# poe_breakout.net
KiCad netlist of a schematic drawn in EAGLE
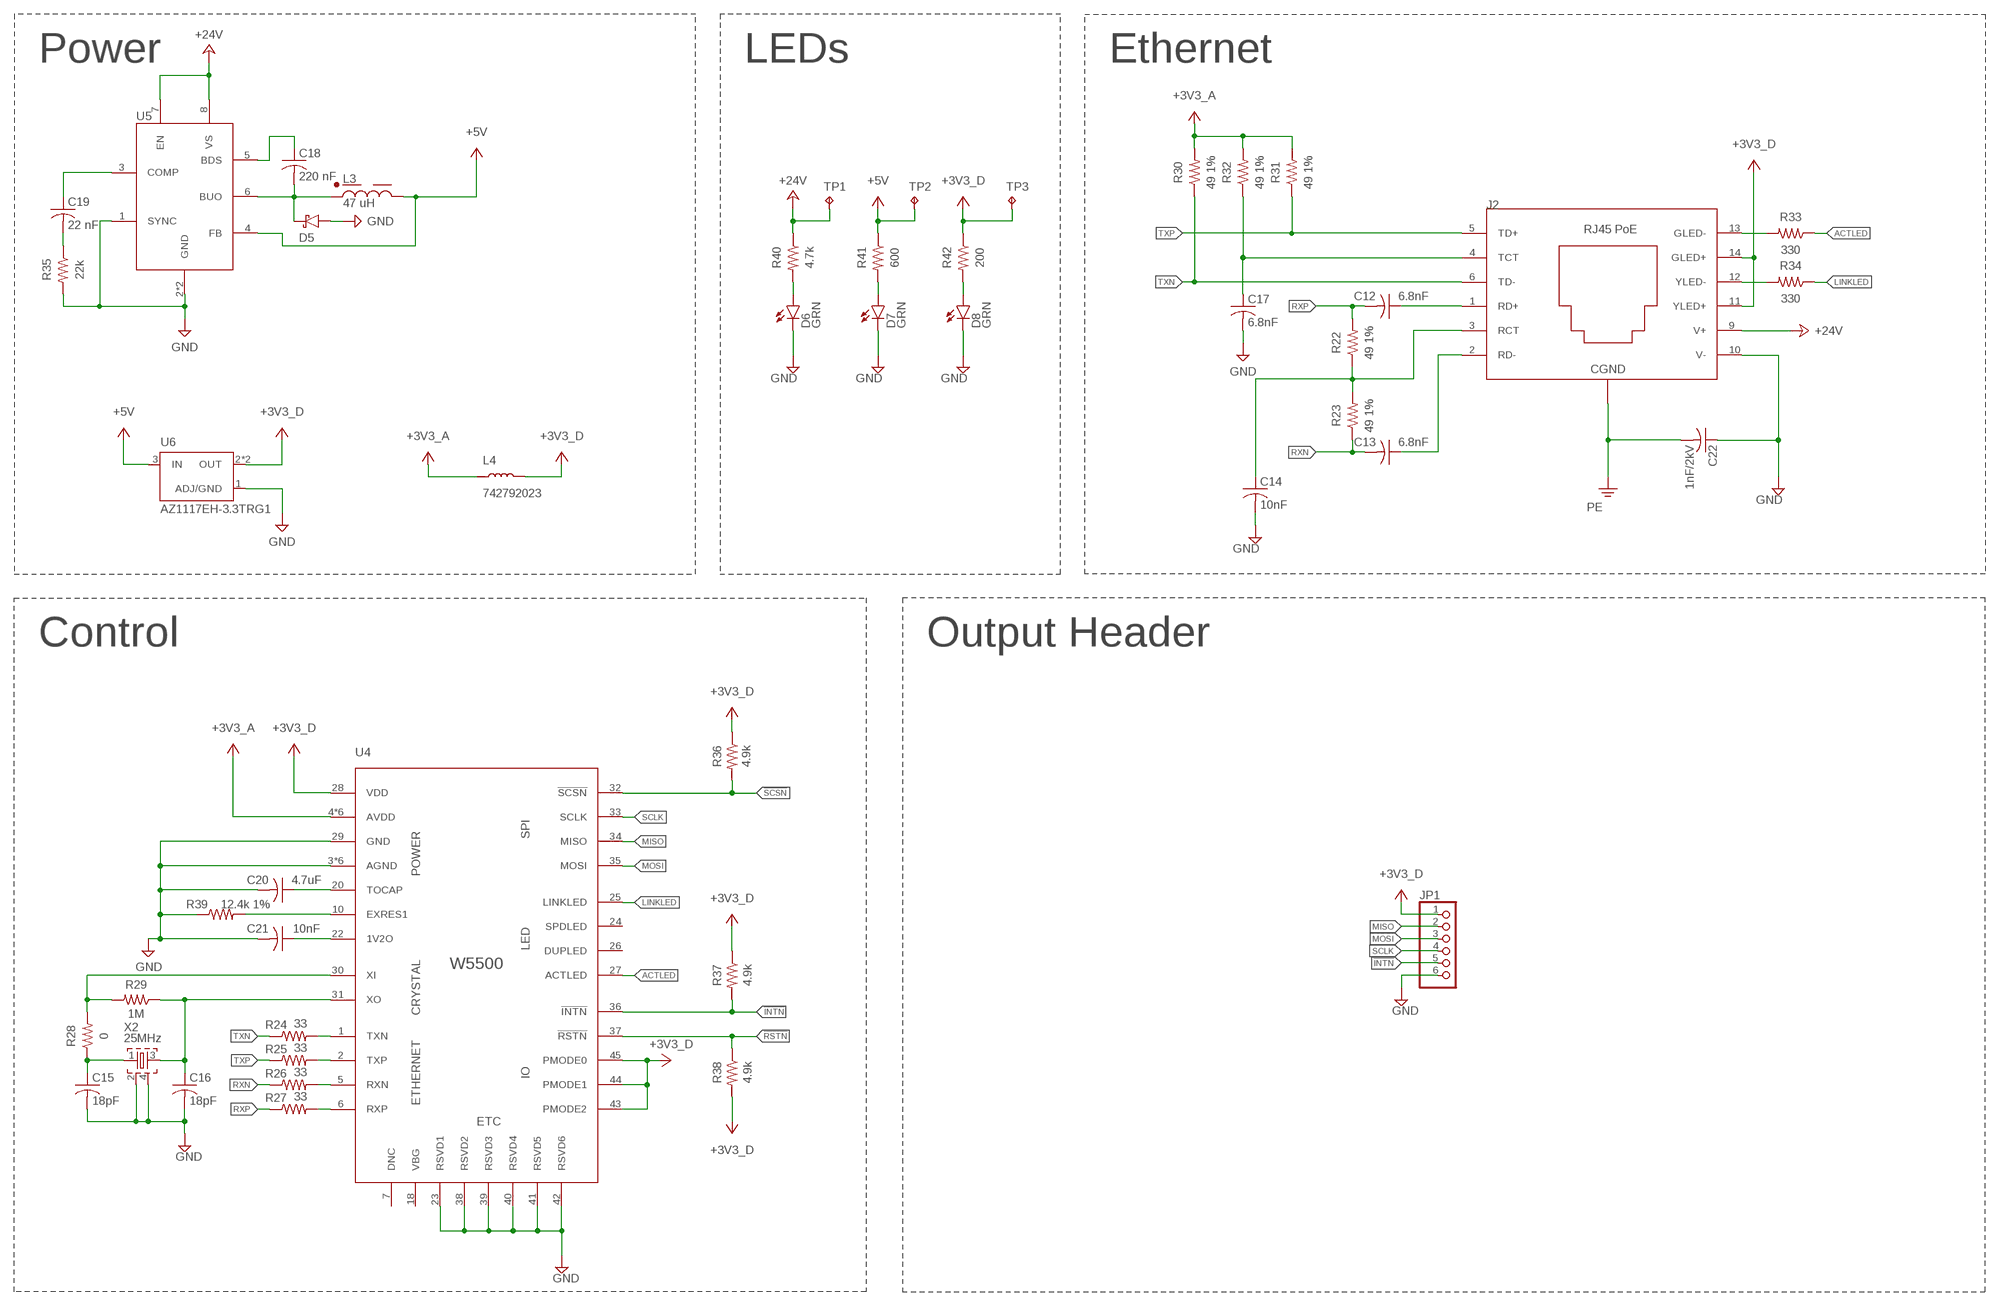
[diagram p0: schematic, sheet 1]

(export (version "E")
  (design (tool "Eeschema 10.0.6"))
  (components
    (comp (ref "C12")
      (value "6.8nF")
      (footprint "eagle-import:C0603")
      (libsource (lib "eagle-import") (part "C-USC0603"))
    )
    (comp (ref "C13")
      (value "6.8nF")
      (footprint "eagle-import:C0603")
      (libsource (lib "eagle-import") (part "C-USC0603"))
    )
    (comp (ref "C14")
      (value "10nF")
      (footprint "eagle-import:C0603")
      (libsource (lib "eagle-import") (part "C-USC0603"))
    )
    (comp (ref "C15")
      (value "18pF")
      (footprint "eagle-import:C0603")
      (libsource (lib "eagle-import") (part "C-USC0603"))
    )
    (comp (ref "C16")
      (value "18pF")
      (footprint "eagle-import:C0603")
      (libsource (lib "eagle-import") (part "C-USC0603"))
    )
    (comp (ref "C17")
      (value "6.8nF")
      (footprint "eagle-import:C0603")
      (libsource (lib "eagle-import") (part "C-USC0603"))
    )
    (comp (ref "C18")
      (value "220 nF")
      (footprint "eagle-import:C0603")
      (libsource (lib "eagle-import") (part "C-USC0603"))
    )
    (comp (ref "C19")
      (value "22 nF")
      (footprint "eagle-import:C0603")
      (libsource (lib "eagle-import") (part "C-USC0603"))
    )
    (comp (ref "C20")
      (value "4.7uF")
      (footprint "eagle-import:C0603")
      (libsource (lib "eagle-import") (part "C-USC0603"))
    )
    (comp (ref "C21")
      (value "10nF")
      (footprint "eagle-import:C0603")
      (libsource (lib "eagle-import") (part "C-USC0603"))
    )
    (comp (ref "C22")
      (value "1nF/2kV")
      (footprint "eagle-import:C1206")
      (libsource (lib "eagle-import") (part "C-USC1206"))
    )
    (comp (ref "D5")
      (value "SCHOTTKYSOD-323")
      (footprint "eagle-import:SOD-323")
      (libsource (lib "eagle-import") (part "SCHOTTKYSOD-323"))
    )
    (comp (ref "D6")
      (value "GRN")
      (footprint "eagle-import:CHIP-LED0603")
      (libsource (lib "eagle-import") (part "LEDCHIP-LED0603"))
    )
    (comp (ref "D7")
      (value "GRN")
      (footprint "eagle-import:CHIP-LED0603")
      (libsource (lib "eagle-import") (part "LEDCHIP-LED0603"))
    )
    (comp (ref "D8")
      (value "GRN")
      (footprint "eagle-import:CHIP-LED0603")
      (libsource (lib "eagle-import") (part "LEDCHIP-LED0603"))
    )
    (comp (ref "J2")
      (value "ARJP11A")
      (footprint "eagle-import:ARJP11A-MBSB-A-B-EMU2")
      (libsource (lib "eagle-import") (part "ARJP11A"))
    )
    (comp (ref "JP1")
      (value "PINHD-1X6")
      (footprint "eagle-import:1X06")
      (libsource (lib "eagle-import") (part "PINHD-1X6"))
    )
    (comp (ref "L3")
      (value "47 uH")
      (footprint "eagle-import:744771147")
      (libsource (lib "eagle-import") (part "744771147"))
    )
    (comp (ref "L4")
      (value "742792023")
      (footprint "eagle-import:0805")
      (libsource (lib "eagle-import") (part "INDUCTOR_0805"))
    )
    (comp (ref "R22")
      (value "49 1%")
      (footprint "eagle-import:R0603")
      (libsource (lib "eagle-import") (part "R-US_R0603"))
    )
    (comp (ref "R23")
      (value "49 1%")
      (footprint "eagle-import:R0603")
      (libsource (lib "eagle-import") (part "R-US_R0603"))
    )
    (comp (ref "R24")
      (value "33")
      (footprint "eagle-import:R0603")
      (libsource (lib "eagle-import") (part "R-US_R0603"))
    )
    (comp (ref "R25")
      (value "33")
      (footprint "eagle-import:R0603")
      (libsource (lib "eagle-import") (part "R-US_R0603"))
    )
    (comp (ref "R26")
      (value "33")
      (footprint "eagle-import:R0603")
      (libsource (lib "eagle-import") (part "R-US_R0603"))
    )
    (comp (ref "R27")
      (value "33")
      (footprint "eagle-import:R0603")
      (libsource (lib "eagle-import") (part "R-US_R0603"))
    )
    (comp (ref "R28")
      (value "0")
      (footprint "eagle-import:R0603")
      (libsource (lib "eagle-import") (part "R-US_R0603"))
    )
    (comp (ref "R29")
      (value "1M")
      (footprint "eagle-import:R0603")
      (libsource (lib "eagle-import") (part "R-US_R0603"))
    )
    (comp (ref "R30")
      (value "49 1%")
      (footprint "eagle-import:R0603")
      (libsource (lib "eagle-import") (part "R-US_R0603"))
    )
    (comp (ref "R31")
      (value "49 1%")
      (footprint "eagle-import:R0603")
      (libsource (lib "eagle-import") (part "R-US_R0603"))
    )
    (comp (ref "R32")
      (value "49 1%")
      (footprint "eagle-import:R0603")
      (libsource (lib "eagle-import") (part "R-US_R0603"))
    )
    (comp (ref "R33")
      (value "330")
      (footprint "eagle-import:R0603")
      (libsource (lib "eagle-import") (part "R-US_R0603"))
    )
    (comp (ref "R34")
      (value "330")
      (footprint "eagle-import:R0603")
      (libsource (lib "eagle-import") (part "R-US_R0603"))
    )
    (comp (ref "R35")
      (value "22k")
      (footprint "eagle-import:R0603")
      (libsource (lib "eagle-import") (part "R-US_R0603"))
    )
    (comp (ref "R36")
      (value "4.9k")
      (footprint "eagle-import:R0603")
      (libsource (lib "eagle-import") (part "R-US_R0603"))
    )
    (comp (ref "R37")
      (value "4.9k")
      (footprint "eagle-import:R0603")
      (libsource (lib "eagle-import") (part "R-US_R0603"))
    )
    (comp (ref "R38")
      (value "4.9k")
      (footprint "eagle-import:R0603")
      (libsource (lib "eagle-import") (part "R-US_R0603"))
    )
    (comp (ref "R39")
      (value "12.4k 1%")
      (footprint "eagle-import:R0603")
      (libsource (lib "eagle-import") (part "R-US_R0603"))
    )
    (comp (ref "R40")
      (value "4.7k")
      (footprint "eagle-import:R0603")
      (libsource (lib "eagle-import") (part "R-US_R0603"))
    )
    (comp (ref "R41")
      (value "600")
      (footprint "eagle-import:R0603")
      (libsource (lib "eagle-import") (part "R-US_R0603"))
    )
    (comp (ref "R42")
      (value "200")
      (footprint "eagle-import:R0603")
      (libsource (lib "eagle-import") (part "R-US_R0603"))
    )
    (comp (ref "TP1")
      (value "TPB1,27")
      (footprint "eagle-import:B1,27")
      (libsource (lib "eagle-import") (part "TPB1,27"))
    )
    (comp (ref "TP2")
      (value "TPB1,27")
      (footprint "eagle-import:B1,27")
      (libsource (lib "eagle-import") (part "TPB1,27"))
    )
    (comp (ref "TP3")
      (value "TPB1,27")
      (footprint "eagle-import:B1,27")
      (libsource (lib "eagle-import") (part "TPB1,27"))
    )
    (comp (ref "U4")
      (value "W5500")
      (footprint "eagle-import:48-LQFP")
      (libsource (lib "eagle-import") (part "W5500"))
    )
    (comp (ref "U5")
      (value "IFX91041")
      (footprint "eagle-import:SOIC-8-EXPOSED_PAD")
      (libsource (lib "eagle-import") (part "IFX91041"))
    )
    (comp (ref "U6")
      (value "AZ1117EH-3.3TRG1")
      (footprint "eagle-import:SOT230P700X180-4N")
      (libsource (lib "eagle-import") (part "AZ1117EH-3.3TRG1"))
    )
    (comp (ref "X2")
      (value "25MHz")
      (footprint "eagle-import:OSCILLATOR-SMD-2.5X2")
      (libsource (lib "eagle-import") (part "ABM10W-25.0000MHZ-6-K1Z-T3"))
    )
  )
  (nets
    (net (code "1") (name "+3V3_A") (class "Default")
      (node (ref "L4") (pin "1") (pinfunction "1_1") (pintype "passive"))
      (node (ref "R30") (pin "2") (pinfunction "2_2") (pintype "passive"))
      (node (ref "R31") (pin "2") (pinfunction "2_2") (pintype "passive"))
      (node (ref "R32") (pin "2") (pinfunction "2_2") (pintype "passive"))
      (node (ref "U4") (pin "11") (pinfunction "AVDD_11") (pintype "power_in"))
      (node (ref "U4") (pin "15") (pinfunction "AVDD_15") (pintype "power_in"))
      (node (ref "U4") (pin "17") (pinfunction "AVDD_17") (pintype "power_in"))
      (node (ref "U4") (pin "21") (pinfunction "AVDD_21") (pintype "power_in"))
      (node (ref "U4") (pin "4") (pinfunction "AVDD_4") (pintype "power_in"))
      (node (ref "U4") (pin "8") (pinfunction "AVDD_8") (pintype "power_in"))
    )
    (net (code "2") (name "+3V3_D") (class "Default")
      (node (ref "J2") (pin "11") (pinfunction "YLED+_11") (pintype "bidirectional"))
      (node (ref "J2") (pin "14") (pinfunction "GLED+_14") (pintype "bidirectional"))
      (node (ref "JP1") (pin "1") (pinfunction "1_1") (pintype "passive"))
      (node (ref "L4") (pin "2") (pinfunction "2_2") (pintype "passive"))
      (node (ref "R36") (pin "1") (pinfunction "1_1") (pintype "passive"))
      (node (ref "R37") (pin "1") (pinfunction "1_1") (pintype "passive"))
      (node (ref "R38") (pin "2") (pinfunction "2_2") (pintype "passive"))
      (node (ref "R42") (pin "1") (pinfunction "1_1") (pintype "passive"))
      (node (ref "TP3") (pin "TP") (pinfunction "TP_TP") (pintype "input"))
      (node (ref "U4") (pin "28") (pinfunction "VDD_28") (pintype "power_in"))
      (node (ref "U4") (pin "43") (pinfunction "PMODE2_43") (pintype "input"))
      (node (ref "U4") (pin "44") (pinfunction "PMODE1_44") (pintype "input"))
      (node (ref "U4") (pin "45") (pinfunction "PMODE0_45") (pintype "input"))
      (node (ref "U6") (pin "2") (pinfunction "OUT_2") (pintype "output"))
      (node (ref "U6") (pin "4") (pinfunction "OUT_4") (pintype "output"))
    )
    (net (code "3") (name "+5V") (class "Default")
      (node (ref "L3") (pin "1") (pinfunction "P$1_1") (pintype "passive"))
      (node (ref "R41") (pin "1") (pinfunction "1_1") (pintype "passive"))
      (node (ref "TP2") (pin "TP") (pinfunction "TP_TP") (pintype "input"))
      (node (ref "U5") (pin "4") (pinfunction "FB_4") (pintype "bidirectional"))
      (node (ref "U6") (pin "3") (pinfunction "IN_3") (pintype "input"))
    )
    (net (code "4") (name "+24V") (class "Default")
      (node (ref "J2") (pin "9") (pinfunction "V+_9") (pintype "bidirectional"))
      (node (ref "R40") (pin "1") (pinfunction "1_1") (pintype "passive"))
      (node (ref "TP1") (pin "TP") (pinfunction "TP_TP") (pintype "input"))
      (node (ref "U5") (pin "7") (pinfunction "EN_7") (pintype "input"))
      (node (ref "U5") (pin "8") (pinfunction "VS_8") (pintype "power_in"))
    )
    (net (code "5") (name "/~{INTN}") (class "Default")
      (node (ref "JP1") (pin "5") (pinfunction "5_5") (pintype "passive"))
      (node (ref "R37") (pin "2") (pinfunction "2_2") (pintype "passive"))
      (node (ref "U4") (pin "36") (pinfunction "~{INTN}_36") (pintype "output"))
    )
    (net (code "6") (name "/~{RSTN}") (class "Default")
      (node (ref "R38") (pin "1") (pinfunction "1_1") (pintype "passive"))
      (node (ref "U4") (pin "37") (pinfunction "~{RSTN}_37") (pintype "input"))
    )
    (net (code "7") (name "/~{SCSN}") (class "Default")
      (node (ref "R36") (pin "2") (pinfunction "2_2") (pintype "passive"))
      (node (ref "U4") (pin "32") (pinfunction "~{SCSN}_32") (pintype "input"))
    )
    (net (code "8") (name "ACTLED") (class "Default")
      (node (ref "R33") (pin "1") (pinfunction "1_1") (pintype "passive"))
      (node (ref "U4") (pin "27") (pinfunction "ACTLED_27") (pintype "output"))
    )
    (net (code "9") (name "GND") (class "Default")
      (node (ref "C14") (pin "2") (pinfunction "2_2") (pintype "passive"))
      (node (ref "C15") (pin "2") (pinfunction "2_2") (pintype "passive"))
      (node (ref "C16") (pin "2") (pinfunction "2_2") (pintype "passive"))
      (node (ref "C17") (pin "2") (pinfunction "2_2") (pintype "passive"))
      (node (ref "C20") (pin "2") (pinfunction "2_2") (pintype "passive"))
      (node (ref "C21") (pin "2") (pinfunction "2_2") (pintype "passive"))
      (node (ref "C22") (pin "1") (pinfunction "1_1") (pintype "passive"))
      (node (ref "D5") (pin "A") (pinfunction "A_A") (pintype "passive"))
      (node (ref "D6") (pin "C") (pinfunction "C_C") (pintype "passive"))
      (node (ref "D7") (pin "C") (pinfunction "C_C") (pintype "passive"))
      (node (ref "D8") (pin "C") (pinfunction "C_C") (pintype "passive"))
      (node (ref "J2") (pin "10") (pinfunction "V-_10") (pintype "bidirectional"))
      (node (ref "JP1") (pin "6") (pinfunction "6_6") (pintype "passive"))
      (node (ref "R35") (pin "2") (pinfunction "2_2") (pintype "passive"))
      (node (ref "R39") (pin "1") (pinfunction "1_1") (pintype "passive"))
      (node (ref "U4") (pin "14") (pinfunction "AGND_14") (pintype "power_in"))
      (node (ref "U4") (pin "16") (pinfunction "AGND_16") (pintype "power_in"))
      (node (ref "U4") (pin "19") (pinfunction "AGND_19") (pintype "power_in"))
      (node (ref "U4") (pin "23") (pinfunction "RSVD1_23") (pintype "input"))
      (node (ref "U4") (pin "29") (pinfunction "GND_29") (pintype "power_in"))
      (node (ref "U4") (pin "3") (pinfunction "AGND_3") (pintype "power_in"))
      (node (ref "U4") (pin "38") (pinfunction "RSVD2_38") (pintype "input"))
      (node (ref "U4") (pin "39") (pinfunction "RSVD3_39") (pintype "input"))
      (node (ref "U4") (pin "40") (pinfunction "RSVD4_40") (pintype "input"))
      (node (ref "U4") (pin "41") (pinfunction "RSVD5_41") (pintype "input"))
      (node (ref "U4") (pin "42") (pinfunction "RSVD6_42") (pintype "input"))
      (node (ref "U4") (pin "48") (pinfunction "AGND_48") (pintype "power_in"))
      (node (ref "U4") (pin "9") (pinfunction "AGND_9") (pintype "power_in"))
      (node (ref "U5") (pin "1") (pinfunction "SYNC_1") (pintype "input"))
      (node (ref "U5") (pin "2") (pinfunction "GND_2") (pintype "power_in"))
      (node (ref "U5") (pin "P$9") (pinfunction "GND_P$9") (pintype "power_in"))
      (node (ref "U6") (pin "1") (pinfunction "ADJ/GND_1") (pintype "power_in"))
      (node (ref "X2") (pin "2") (pinfunction "SHD1_2") (pintype "passive"))
      (node (ref "X2") (pin "4") (pinfunction "SHD2_4") (pintype "passive"))
    )
    (net (code "10") (name "LINKLED") (class "Default")
      (node (ref "R34") (pin "1") (pinfunction "1_1") (pintype "passive"))
      (node (ref "U4") (pin "25") (pinfunction "LINKLED_25") (pintype "output"))
    )
    (net (code "11") (name "MISO") (class "Default")
      (node (ref "JP1") (pin "2") (pinfunction "2_2") (pintype "passive"))
      (node (ref "U4") (pin "34") (pinfunction "MISO_34") (pintype "output"))
    )
    (net (code "12") (name "MOSI") (class "Default")
      (node (ref "JP1") (pin "3") (pinfunction "3_3") (pintype "passive"))
      (node (ref "U4") (pin "35") (pinfunction "MOSI_35") (pintype "input"))
    )
    (net (code "13") (name "Net-(C19-Pad2)") (class "Default")
      (node (ref "C19") (pin "2") (pinfunction "2_2") (pintype "passive"))
      (node (ref "R35") (pin "1") (pinfunction "1_1") (pintype "passive"))
    )
    (net (code "14") (name "Net-(D6-PadA)") (class "Default")
      (node (ref "D6") (pin "A") (pinfunction "A_A") (pintype "passive"))
      (node (ref "R40") (pin "2") (pinfunction "2_2") (pintype "passive"))
    )
    (net (code "15") (name "Net-(D7-PadA)") (class "Default")
      (node (ref "D7") (pin "A") (pinfunction "A_A") (pintype "passive"))
      (node (ref "R41") (pin "2") (pinfunction "2_2") (pintype "passive"))
    )
    (net (code "16") (name "Net-(D8-PadA)") (class "Default")
      (node (ref "D8") (pin "A") (pinfunction "A_A") (pintype "passive"))
      (node (ref "R42") (pin "2") (pinfunction "2_2") (pintype "passive"))
    )
    (net (code "17") (name "Net-(J2-GLED-)") (class "Default")
      (node (ref "J2") (pin "13") (pinfunction "GLED-_13") (pintype "bidirectional"))
      (node (ref "R33") (pin "2") (pinfunction "2_2") (pintype "passive"))
    )
    (net (code "18") (name "Net-(J2-RCT)") (class "Default")
      (node (ref "C14") (pin "1") (pinfunction "1_1") (pintype "passive"))
      (node (ref "J2") (pin "3") (pinfunction "RCT_3") (pintype "bidirectional"))
      (node (ref "R22") (pin "1") (pinfunction "1_1") (pintype "passive"))
      (node (ref "R23") (pin "2") (pinfunction "2_2") (pintype "passive"))
    )
    (net (code "19") (name "Net-(J2-RD+)") (class "Default")
      (node (ref "C12") (pin "1") (pinfunction "1_1") (pintype "passive"))
      (node (ref "J2") (pin "1") (pinfunction "RD+_1") (pintype "bidirectional"))
    )
    (net (code "20") (name "Net-(J2-RD-)") (class "Default")
      (node (ref "C13") (pin "1") (pinfunction "1_1") (pintype "passive"))
      (node (ref "J2") (pin "2") (pinfunction "RD-_2") (pintype "bidirectional"))
    )
    (net (code "21") (name "Net-(J2-TCT)") (class "Default")
      (node (ref "C17") (pin "1") (pinfunction "1_1") (pintype "passive"))
      (node (ref "J2") (pin "4") (pinfunction "TCT_4") (pintype "bidirectional"))
      (node (ref "R32") (pin "1") (pinfunction "1_1") (pintype "passive"))
    )
    (net (code "22") (name "Net-(J2-YLED-)") (class "Default")
      (node (ref "J2") (pin "12") (pinfunction "YLED-_12") (pintype "bidirectional"))
      (node (ref "R34") (pin "2") (pinfunction "2_2") (pintype "passive"))
    )
    (net (code "23") (name "Net-(U4-1V2O)") (class "Default")
      (node (ref "C21") (pin "1") (pinfunction "1_1") (pintype "passive"))
      (node (ref "U4") (pin "22") (pinfunction "1V2O_22") (pintype "output"))
    )
    (net (code "24") (name "Net-(U4-EXRES1)") (class "Default")
      (node (ref "R39") (pin "2") (pinfunction "2_2") (pintype "passive"))
      (node (ref "U4") (pin "10") (pinfunction "EXRES1_10") (pintype "output"))
    )
    (net (code "25") (name "Net-(U4-RXN)") (class "Default")
      (node (ref "R26") (pin "2") (pinfunction "2_2") (pintype "passive"))
      (node (ref "U4") (pin "5") (pinfunction "RXN_5") (pintype "input"))
    )
    (net (code "26") (name "Net-(U4-RXP)") (class "Default")
      (node (ref "R27") (pin "2") (pinfunction "2_2") (pintype "passive"))
      (node (ref "U4") (pin "6") (pinfunction "RXP_6") (pintype "input"))
    )
    (net (code "27") (name "Net-(U4-TOCAP)") (class "Default")
      (node (ref "C20") (pin "1") (pinfunction "1_1") (pintype "passive"))
      (node (ref "U4") (pin "20") (pinfunction "TOCAP_20") (pintype "output"))
    )
    (net (code "28") (name "Net-(U4-TXN)") (class "Default")
      (node (ref "R24") (pin "2") (pinfunction "2_2") (pintype "passive"))
      (node (ref "U4") (pin "1") (pinfunction "TXN_1") (pintype "output"))
    )
    (net (code "29") (name "Net-(U4-TXP)") (class "Default")
      (node (ref "R25") (pin "2") (pinfunction "2_2") (pintype "passive"))
      (node (ref "U4") (pin "2") (pinfunction "TXP_2") (pintype "output"))
    )
    (net (code "30") (name "Net-(U4-XI)") (class "Default")
      (node (ref "R28") (pin "2") (pinfunction "2_2") (pintype "passive"))
      (node (ref "R29") (pin "2") (pinfunction "2_2") (pintype "passive"))
      (node (ref "U4") (pin "30") (pinfunction "XI_30") (pintype "bidirectional"))
    )
    (net (code "31") (name "Net-(U4-XO)") (class "Default")
      (node (ref "C16") (pin "1") (pinfunction "1_1") (pintype "passive"))
      (node (ref "R29") (pin "1") (pinfunction "1_1") (pintype "passive"))
      (node (ref "U4") (pin "31") (pinfunction "XO_31") (pintype "bidirectional"))
      (node (ref "X2") (pin "3") (pinfunction "OUT_3") (pintype "passive"))
    )
    (net (code "32") (name "Net-(U5-BDS)") (class "Default")
      (node (ref "C18") (pin "1") (pinfunction "1_1") (pintype "passive"))
      (node (ref "U5") (pin "5") (pinfunction "BDS_5") (pintype "bidirectional"))
    )
    (net (code "33") (name "Net-(U5-BUO)") (class "Default")
      (node (ref "C18") (pin "2") (pinfunction "2_2") (pintype "passive"))
      (node (ref "D5") (pin "C") (pinfunction "C_C") (pintype "passive"))
      (node (ref "L3") (pin "P$2") (pinfunction "P$2_P$2") (pintype "passive"))
      (node (ref "U5") (pin "6") (pinfunction "BUO_6") (pintype "bidirectional"))
    )
    (net (code "34") (name "Net-(U5-COMP)") (class "Default")
      (node (ref "C19") (pin "1") (pinfunction "1_1") (pintype "passive"))
      (node (ref "U5") (pin "3") (pinfunction "COMP_3") (pintype "bidirectional"))
    )
    (net (code "35") (name "Net-(X2-IN)") (class "Default")
      (node (ref "C15") (pin "1") (pinfunction "1_1") (pintype "passive"))
      (node (ref "R28") (pin "1") (pinfunction "1_1") (pintype "passive"))
      (node (ref "X2") (pin "1") (pinfunction "IN_1") (pintype "passive"))
    )
    (net (code "36") (name "PE") (class "Default")
      (node (ref "C22") (pin "2") (pinfunction "2_2") (pintype "passive"))
      (node (ref "J2") (pin "15") (pinfunction "CGND_15") (pintype "bidirectional"))
      (node (ref "J2") (pin "16") (pinfunction "CGND_16") (pintype "bidirectional"))
    )
    (net (code "37") (name "RXN") (class "Default")
      (node (ref "C13") (pin "2") (pinfunction "2_2") (pintype "passive"))
      (node (ref "R23") (pin "1") (pinfunction "1_1") (pintype "passive"))
      (node (ref "R26") (pin "1") (pinfunction "1_1") (pintype "passive"))
    )
    (net (code "38") (name "RXP") (class "Default")
      (node (ref "C12") (pin "2") (pinfunction "2_2") (pintype "passive"))
      (node (ref "R22") (pin "2") (pinfunction "2_2") (pintype "passive"))
      (node (ref "R27") (pin "1") (pinfunction "1_1") (pintype "passive"))
    )
    (net (code "39") (name "SCLK") (class "Default")
      (node (ref "JP1") (pin "4") (pinfunction "4_4") (pintype "passive"))
      (node (ref "U4") (pin "33") (pinfunction "SCLK_33") (pintype "input"))
    )
    (net (code "40") (name "TXN") (class "Default")
      (node (ref "J2") (pin "6") (pinfunction "TD-_6") (pintype "bidirectional"))
      (node (ref "R24") (pin "1") (pinfunction "1_1") (pintype "passive"))
      (node (ref "R30") (pin "1") (pinfunction "1_1") (pintype "passive"))
    )
    (net (code "41") (name "TXP") (class "Default")
      (node (ref "J2") (pin "5") (pinfunction "TD+_5") (pintype "bidirectional"))
      (node (ref "R25") (pin "1") (pinfunction "1_1") (pintype "passive"))
      (node (ref "R31") (pin "1") (pinfunction "1_1") (pintype "passive"))
    )
    (net (code "42") (name "unconnected-(U4-DNC-Pad7)") (class "Default")
      (node (ref "U4") (pin "7") (pinfunction "DNC_7") (pintype "no_connect"))
    )
    (net (code "43") (name "unconnected-(U4-DUPLED-Pad26)") (class "Default")
      (node (ref "U4") (pin "26") (pinfunction "DUPLED_26") (pintype "output"))
    )
    (net (code "44") (name "unconnected-(U4-SPDLED-Pad24)") (class "Default")
      (node (ref "U4") (pin "24") (pinfunction "SPDLED_24") (pintype "output"))
    )
    (net (code "45") (name "unconnected-(U4-VBG-Pad18)") (class "Default")
      (node (ref "U4") (pin "18") (pinfunction "VBG_18") (pintype "no_connect"))
    )
  )
)
